# MCU.net
KiCad netlist of a schematic drawn in Altium Designer
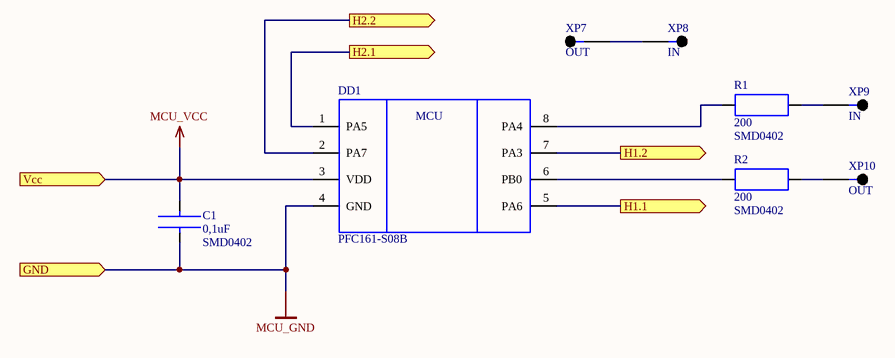
[diagram p0: MCU.SchDoc]

(export (version "E")
  (design (tool "Eeschema 10.0.6"))
  (components
    (comp (ref "C1")
      (value "0,1uF")
      (footprint "SMD0402(1608)")
      (fields (field (name "PACKAGE") "SMD0402"))
      (libsource (lib "MechanikLibrary") (part "CER_CUP_0402"))
    )
    (comp (ref "DD1")
      (value "PFC161-S08B")
      (footprint "SOIC8")
      (libsource (lib "MechanikLibrary") (part "PFC161-S08B"))
    )
    (comp (ref "R1")
      (value "200")
      (footprint "SMD0402(1608)")
      (fields (field (name "PACKAGE") "SMD0402"))
      (libsource (lib "MechanikLibrary") (part "R_0402"))
    )
    (comp (ref "R2")
      (value "200")
      (footprint "SMD0402(1608)")
      (fields (field (name "PACKAGE") "SMD0402"))
      (libsource (lib "MechanikLibrary") (part "R_0402"))
    )
    (comp (ref "XP7")
      (value "OUT")
      (footprint "XP_solder")
      (libsource (lib "MechanikLibrary") (part "XP_solder"))
    )
    (comp (ref "XP8")
      (value "IN")
      (footprint "XP_solder")
      (libsource (lib "MechanikLibrary") (part "XP_solder"))
    )
    (comp (ref "XP9")
      (value "IN")
      (footprint "XP_solder")
      (libsource (lib "MechanikLibrary") (part "XP_solder"))
    )
    (comp (ref "XP10")
      (value "OUT")
      (footprint "XP_solder")
      (libsource (lib "MechanikLibrary") (part "XP_solder"))
    )
  )
  (nets
    (net (code "1") (name "/H1.1") (class "Default")
      (node (ref "DD1") (pin "5") (pinfunction "PA6_5") (pintype "passive"))
    )
    (net (code "2") (name "/H1.2") (class "Default")
      (node (ref "DD1") (pin "7") (pinfunction "PA3_7") (pintype "passive"))
    )
    (net (code "3") (name "/H2.1") (class "Default")
      (node (ref "DD1") (pin "1") (pinfunction "PA5_1") (pintype "passive"))
    )
    (net (code "4") (name "/H2.2") (class "Default")
      (node (ref "DD1") (pin "2") (pinfunction "PA7_2") (pintype "passive"))
    )
    (net (code "5") (name "MCU_GND") (class "Default")
      (node (ref "C1") (pin "2") (pintype "passive"))
      (node (ref "DD1") (pin "4") (pinfunction "GND_4") (pintype "passive"))
    )
    (net (code "6") (name "MCU_VCC") (class "Default")
      (node (ref "C1") (pin "1") (pintype "passive"))
      (node (ref "DD1") (pin "3") (pinfunction "VDD_3") (pintype "passive"))
    )
    (net (code "7") (name "Net-(DD1-PA4)") (class "Default")
      (node (ref "DD1") (pin "8") (pinfunction "PA4_8") (pintype "passive"))
      (node (ref "R1") (pin "1") (pintype "passive"))
    )
    (net (code "8") (name "Net-(DD1-PB0)") (class "Default")
      (node (ref "DD1") (pin "6") (pinfunction "PB0_6") (pintype "passive"))
      (node (ref "R2") (pin "1") (pintype "passive"))
    )
    (net (code "9") (name "Net-(R1-Pad2)") (class "Default")
      (node (ref "R1") (pin "2") (pintype "passive"))
      (node (ref "XP9") (pin "1") (pinfunction "1_1") (pintype "passive"))
    )
    (net (code "10") (name "Net-(R2-Pad2)") (class "Default")
      (node (ref "R2") (pin "2") (pintype "passive"))
      (node (ref "XP10") (pin "1") (pinfunction "1_1") (pintype "passive"))
    )
    (net (code "11") (name "Net-(XP7-Pad1)") (class "Default")
      (node (ref "XP7") (pin "1") (pinfunction "1_1") (pintype "passive"))
      (node (ref "XP8") (pin "1") (pinfunction "1_1") (pintype "passive"))
    )
  )
)
